# FI-pi_Milanpreet_Singh.net
KiCad netlist of a schematic drawn in EAGLE
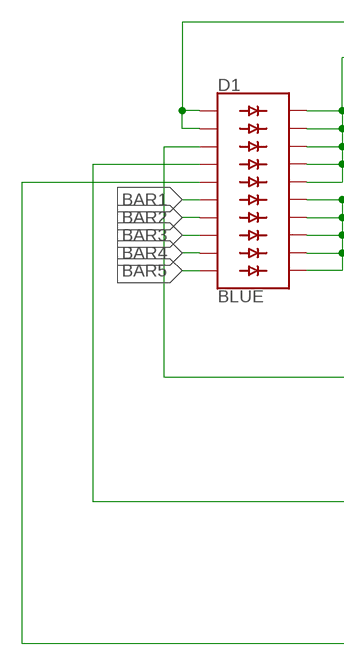
[diagram p0: schematic, sheet 1, part 1 of 2]
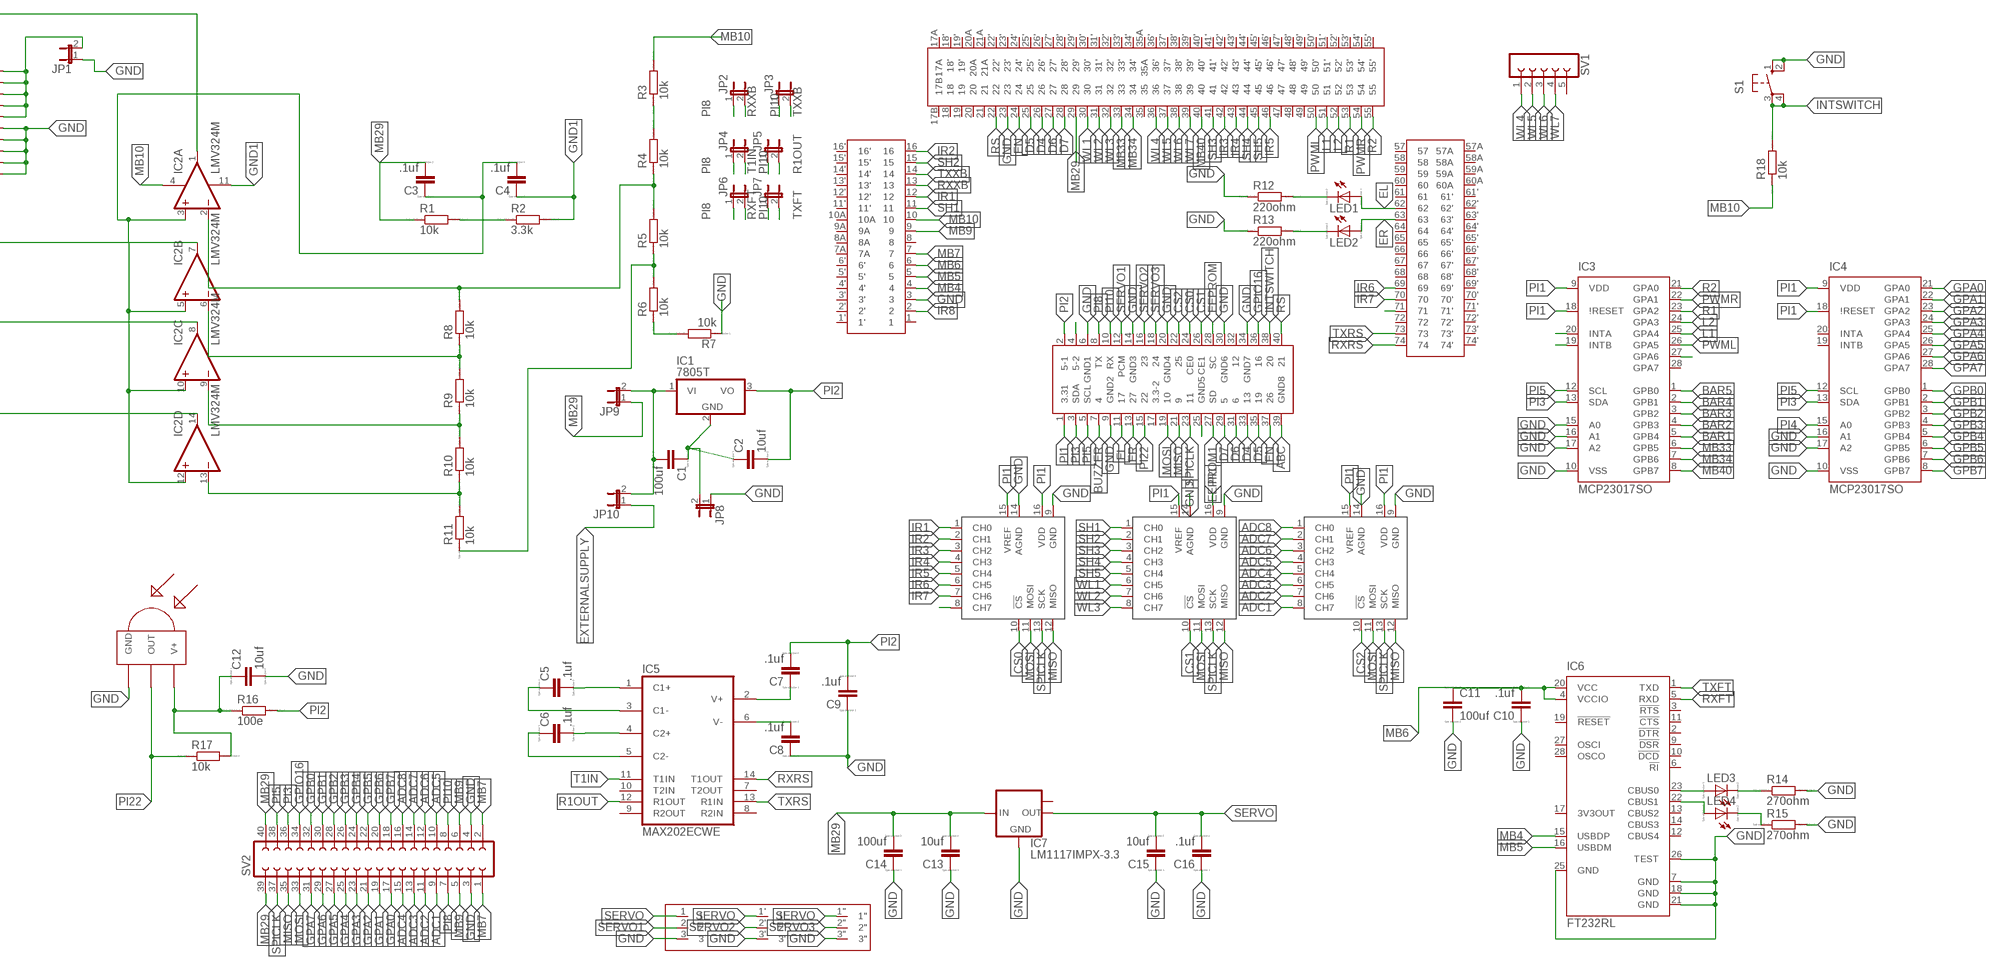
[diagram p1: schematic, sheet 1, part 2 of 2]

(export (version "E")
  (design (tool "Eeschema 10.0.6"))
  (components
    (comp (ref "C1")
      (value "100uf")
      (footprint "eagle-import:C1206")
      (libsource (lib "eagle-import") (part "CC1206"))
    )
    (comp (ref "C2")
      (value "10uf")
      (footprint "eagle-import:C1206")
      (libsource (lib "eagle-import") (part "CC1206"))
    )
    (comp (ref "C3")
      (value ".1uf")
      (footprint "eagle-import:C1206")
      (libsource (lib "eagle-import") (part "CC1206"))
    )
    (comp (ref "C4")
      (value ".1uf")
      (footprint "eagle-import:C1206")
      (libsource (lib "eagle-import") (part "CC1206"))
    )
    (comp (ref "C5")
      (value ".1uf")
      (footprint "eagle-import:C1206")
      (libsource (lib "eagle-import") (part "CC1206"))
    )
    (comp (ref "C6")
      (value ".1uf")
      (footprint "eagle-import:C1206")
      (libsource (lib "eagle-import") (part "CC1206"))
    )
    (comp (ref "C7")
      (value ".1uf")
      (footprint "eagle-import:C1206")
      (libsource (lib "eagle-import") (part "CC1206"))
    )
    (comp (ref "C8")
      (value ".1uf")
      (footprint "eagle-import:C1206")
      (libsource (lib "eagle-import") (part "CC1206"))
    )
    (comp (ref "C9")
      (value ".1uf")
      (footprint "eagle-import:C1206")
      (libsource (lib "eagle-import") (part "CC1206"))
    )
    (comp (ref "C10")
      (value ".1uf")
      (footprint "eagle-import:C1206")
      (libsource (lib "eagle-import") (part "CC1206"))
    )
    (comp (ref "C11")
      (value "100uf")
      (footprint "eagle-import:C1206")
      (libsource (lib "eagle-import") (part "CC1206"))
    )
    (comp (ref "C12")
      (value "10uf")
      (footprint "eagle-import:C1206")
      (libsource (lib "eagle-import") (part "CC1206"))
    )
    (comp (ref "C13")
      (value "10uf")
      (footprint "eagle-import:C1206")
      (libsource (lib "eagle-import") (part "CC1206"))
    )
    (comp (ref "C14")
      (value "100uf")
      (footprint "eagle-import:C1206")
      (libsource (lib "eagle-import") (part "CC1206"))
    )
    (comp (ref "C15")
      (value "10uf")
      (footprint "eagle-import:C1206")
      (libsource (lib "eagle-import") (part "CC1206"))
    )
    (comp (ref "C16")
      (value ".1uf")
      (footprint "eagle-import:C1206")
      (libsource (lib "eagle-import") (part "CC1206"))
    )
    (comp (ref "D1")
      (value "BLUE")
      (footprint "eagle-import:LED_BARGRAPH_10")
      (libsource (lib "eagle-import") (part "LED_BARGRAPH_10BLUE"))
    )
    (comp (ref "IC1")
      (value "7805T")
      (footprint "eagle-import:TO220H")
      (libsource (lib "eagle-import") (part "78T05"))
    )
    (comp (ref "IC2")
      (value "LMV324M")
      (footprint "eagle-import:SO14")
      (libsource (lib "eagle-import") (part "LMV324?M"))
    )
    (comp (ref "IC3")
      (value "MCP23017SO")
      (footprint "eagle-import:SO28W")
      (libsource (lib "eagle-import") (part "MCP23017SO"))
    )
    (comp (ref "IC4")
      (value "MCP23017SO")
      (footprint "eagle-import:SO28W")
      (libsource (lib "eagle-import") (part "MCP23017SO"))
    )
    (comp (ref "IC5")
      (value "MAX202ECWE")
      (footprint "eagle-import:SO16L")
      (fields (field (name "MPN") "MAX202ECWE+T"))
      (libsource (lib "eagle-import") (part "MAX202ECWE"))
    )
    (comp (ref "IC6")
      (value "FT232RL")
      (footprint "eagle-import:SSOP28")
      (libsource (lib "eagle-import") (part "FT232RL"))
    )
    (comp (ref "IC7")
      (value "LM1117IMPX-3.3")
      (footprint "eagle-import:SOT223")
      (libsource (lib "eagle-import") (part "LM1117IMPX-3.3"))
    )
    (comp (ref "JP1")
      (value "JP1E")
      (footprint "eagle-import:JP1")
      (libsource (lib "eagle-import") (part "JP1E"))
    )
    (comp (ref "JP2")
      (value "JP1E")
      (footprint "eagle-import:JP1")
      (libsource (lib "eagle-import") (part "JP1E"))
    )
    (comp (ref "JP3")
      (value "JP1E")
      (footprint "eagle-import:JP1")
      (libsource (lib "eagle-import") (part "JP1E"))
    )
    (comp (ref "JP4")
      (value "JP1E")
      (footprint "eagle-import:JP1")
      (libsource (lib "eagle-import") (part "JP1E"))
    )
    (comp (ref "JP5")
      (value "JP1E")
      (footprint "eagle-import:JP1")
      (libsource (lib "eagle-import") (part "JP1E"))
    )
    (comp (ref "JP6")
      (value "JP1E")
      (footprint "eagle-import:JP1")
      (libsource (lib "eagle-import") (part "JP1E"))
    )
    (comp (ref "JP7")
      (value "JP1E")
      (footprint "eagle-import:JP1")
      (libsource (lib "eagle-import") (part "JP1E"))
    )
    (comp (ref "JP8")
      (value "JP1E")
      (footprint "eagle-import:JP1")
      (libsource (lib "eagle-import") (part "JP1E"))
    )
    (comp (ref "JP9")
      (value "JP1E")
      (footprint "eagle-import:JP1")
      (libsource (lib "eagle-import") (part "JP1E"))
    )
    (comp (ref "JP10")
      (value "JP1E")
      (footprint "eagle-import:JP1")
      (libsource (lib "eagle-import") (part "JP1E"))
    )
    (comp (ref "LED1")
      (value "LED_E")
      (footprint "eagle-import:LED_1206")
      (libsource (lib "eagle-import") (part "LED_E"))
    )
    (comp (ref "LED2")
      (value "LED_E")
      (footprint "eagle-import:LED_1206")
      (libsource (lib "eagle-import") (part "LED_E"))
    )
    (comp (ref "LED3")
      (value "LED_E")
      (footprint "eagle-import:LED_1206")
      (libsource (lib "eagle-import") (part "LED_E"))
    )
    (comp (ref "LED4")
      (value "LED_E")
      (footprint "eagle-import:LED_1206")
      (libsource (lib "eagle-import") (part "LED_E"))
    )
    (comp (ref "R1")
      (value "10k")
      (footprint "eagle-import:R1206")
      (libsource (lib "eagle-import") (part "RR1206"))
    )
    (comp (ref "R2")
      (value "3.3k")
      (footprint "eagle-import:R1206")
      (libsource (lib "eagle-import") (part "RR1206"))
    )
    (comp (ref "R3")
      (value "10k")
      (footprint "eagle-import:R1206")
      (libsource (lib "eagle-import") (part "RR1206"))
    )
    (comp (ref "R4")
      (value "10k")
      (footprint "eagle-import:R1206")
      (libsource (lib "eagle-import") (part "RR1206"))
    )
    (comp (ref "R5")
      (value "10k")
      (footprint "eagle-import:R1206")
      (libsource (lib "eagle-import") (part "RR1206"))
    )
    (comp (ref "R6")
      (value "10k")
      (footprint "eagle-import:R1206")
      (libsource (lib "eagle-import") (part "RR1206"))
    )
    (comp (ref "R7")
      (value "10k")
      (footprint "eagle-import:R1206")
      (libsource (lib "eagle-import") (part "RR1206"))
    )
    (comp (ref "R8")
      (value "10k")
      (footprint "eagle-import:R1206")
      (libsource (lib "eagle-import") (part "RR1206"))
    )
    (comp (ref "R9")
      (value "10k")
      (footprint "eagle-import:R1206")
      (libsource (lib "eagle-import") (part "RR1206"))
    )
    (comp (ref "R10")
      (value "10k")
      (footprint "eagle-import:R1206")
      (libsource (lib "eagle-import") (part "RR1206"))
    )
    (comp (ref "R11")
      (value "10k")
      (footprint "eagle-import:R1206")
      (libsource (lib "eagle-import") (part "RR1206"))
    )
    (comp (ref "R12")
      (value "220ohm")
      (footprint "eagle-import:R1206")
      (libsource (lib "eagle-import") (part "RR1206"))
    )
    (comp (ref "R13")
      (value "220ohm")
      (footprint "eagle-import:R1206")
      (libsource (lib "eagle-import") (part "RR1206"))
    )
    (comp (ref "R14")
      (value "270ohm")
      (footprint "eagle-import:R1206")
      (libsource (lib "eagle-import") (part "RR1206"))
    )
    (comp (ref "R15")
      (value "270ohm")
      (footprint "eagle-import:R1206")
      (libsource (lib "eagle-import") (part "RR1206"))
    )
    (comp (ref "R16")
      (value "100e")
      (footprint "eagle-import:R1206")
      (libsource (lib "eagle-import") (part "RR1206"))
    )
    (comp (ref "R17")
      (value "10k")
      (footprint "eagle-import:R1206")
      (libsource (lib "eagle-import") (part "RR1206"))
    )
    (comp (ref "R18")
      (value "10k")
      (footprint "eagle-import:R1206")
      (libsource (lib "eagle-import") (part "RR1206"))
    )
    (comp (ref "S1")
      (value "10-XX")
      (footprint "eagle-import:B3F-10XX")
      (fields (field (name "MPN") "B3F-1000"))
      (libsource (lib "eagle-import") (part "10-XX"))
    )
    (comp (ref "SV1")
      (value "FE05-1")
      (footprint "eagle-import:FE05-1")
      (libsource (lib "eagle-import") (part "FE05-1"))
    )
    (comp (ref "SV2")
      (value "FE20-2")
      (footprint "eagle-import:FE20-2")
      (libsource (lib "eagle-import") (part "FE20-2"))
    )
    (comp (ref "U$1")
      (value "DAUGHTERBOARDDAUGHTERBOARD")
      (footprint "eagle-import:DAUGHTERBOARD")
      (libsource (lib "eagle-import") (part "DAUGHTERBOARDDAUGHTERBOARD"))
    )
    (comp (ref "U$2")
      (value "MALE_HEADER")
      (footprint "eagle-import:MALE_HEADER_PACKAGE")
      (libsource (lib "eagle-import") (part "MALE_HEADER"))
    )
    (comp (ref "U$3")
      (value "MCP3008SL")
      (footprint "eagle-import:SO16")
      (libsource (lib "eagle-import") (part "MCP3008SL"))
    )
    (comp (ref "U$4")
      (value "MCP3008SL")
      (footprint "eagle-import:SO16")
      (libsource (lib "eagle-import") (part "MCP3008SL"))
    )
    (comp (ref "U$5")
      (value "MCP3008SL")
      (footprint "eagle-import:SO16")
      (libsource (lib "eagle-import") (part "MCP3008SL"))
    )
    (comp (ref "U$6")
      (value "TSOP1738")
      (footprint "eagle-import:TSOP17XX")
      (libsource (lib "eagle-import") (part "TSOP1738"))
    )
    (comp (ref "U$7")
      (value "SERVO")
      (footprint "eagle-import:SERVO")
      (libsource (lib "eagle-import") (part "SERVO"))
    )
  )
  (nets
    (net (code "1") (name "ABC") (class "Default")
      (node (ref "U$2") (pin "39") (pinfunction "GND8_39") (pintype "bidirectional"))
    )
    (net (code "2") (name "ADC1") (class "Default")
      (node (ref "SV2") (pin "9") (pinfunction "9_9") (pintype "passive"))
      (node (ref "U$5") (pin "8") (pinfunction "CH7_8") (pintype "input"))
    )
    (net (code "3") (name "ADC2") (class "Default")
      (node (ref "SV2") (pin "11") (pinfunction "11_11") (pintype "passive"))
      (node (ref "U$5") (pin "7") (pinfunction "CH6_7") (pintype "input"))
    )
    (net (code "4") (name "ADC3") (class "Default")
      (node (ref "SV2") (pin "13") (pinfunction "13_13") (pintype "passive"))
      (node (ref "U$5") (pin "6") (pinfunction "CH5_6") (pintype "input"))
    )
    (net (code "5") (name "ADC4") (class "Default")
      (node (ref "SV2") (pin "15") (pinfunction "15_15") (pintype "passive"))
      (node (ref "U$5") (pin "5") (pinfunction "CH4_5") (pintype "input"))
    )
    (net (code "6") (name "ADC5") (class "Default")
      (node (ref "SV2") (pin "10") (pinfunction "10_10") (pintype "passive"))
      (node (ref "U$5") (pin "4") (pinfunction "CH3_4") (pintype "input"))
    )
    (net (code "7") (name "ADC6") (class "Default")
      (node (ref "SV2") (pin "12") (pinfunction "12_12") (pintype "passive"))
      (node (ref "U$5") (pin "3") (pinfunction "CH2_3") (pintype "input"))
    )
    (net (code "8") (name "ADC7") (class "Default")
      (node (ref "SV2") (pin "14") (pinfunction "14_14") (pintype "passive"))
      (node (ref "U$5") (pin "2") (pinfunction "CH1_2") (pintype "input"))
    )
    (net (code "9") (name "ADC8") (class "Default")
      (node (ref "SV2") (pin "16") (pinfunction "16_16") (pintype "passive"))
      (node (ref "U$5") (pin "1") (pinfunction "CH0_1") (pintype "input"))
    )
    (net (code "10") (name "BAR1") (class "Default")
      (node (ref "D1") (pin "6") (pinfunction "A5_6") (pintype "passive"))
      (node (ref "IC3") (pin "5") (pinfunction "GPB4_5") (pintype "bidirectional"))
    )
    (net (code "11") (name "BAR2") (class "Default")
      (node (ref "D1") (pin "7") (pinfunction "A6_7") (pintype "passive"))
      (node (ref "IC3") (pin "4") (pinfunction "GPB3_4") (pintype "bidirectional"))
    )
    (net (code "12") (name "BAR3") (class "Default")
      (node (ref "D1") (pin "8") (pinfunction "A7_8") (pintype "passive"))
      (node (ref "IC3") (pin "3") (pinfunction "GPB2_3") (pintype "bidirectional"))
    )
    (net (code "13") (name "BAR4") (class "Default")
      (node (ref "D1") (pin "9") (pinfunction "A8_9") (pintype "passive"))
      (node (ref "IC3") (pin "2") (pinfunction "GPB1_2") (pintype "bidirectional"))
    )
    (net (code "14") (name "BAR5") (class "Default")
      (node (ref "D1") (pin "10") (pinfunction "A9_10") (pintype "passive"))
      (node (ref "IC3") (pin "1") (pinfunction "GPB0_1") (pintype "bidirectional"))
    )
    (net (code "15") (name "BUZZER") (class "Default")
      (node (ref "U$1") (pin "71") (pinfunction "71_71") (pintype "output"))
      (node (ref "U$2") (pin "7") (pinfunction "4_7") (pintype "bidirectional"))
    )
    (net (code "16") (name "CS0") (class "Default")
      (node (ref "U$2") (pin "24") (pinfunction "CE0_24") (pintype "bidirectional"))
      (node (ref "U$3") (pin "10") (pinfunction "~{CS}_10") (pintype "input"))
    )
    (net (code "17") (name "CS1") (class "Default")
      (node (ref "U$2") (pin "26") (pinfunction "CE1_26") (pintype "bidirectional"))
      (node (ref "U$4") (pin "10") (pinfunction "~{CS}_10") (pintype "input"))
    )
    (net (code "18") (name "CS2") (class "Default")
      (node (ref "U$2") (pin "22") (pinfunction "25_22") (pintype "bidirectional"))
      (node (ref "U$5") (pin "10") (pinfunction "~{CS}_10") (pintype "input"))
    )
    (net (code "19") (name "D4") (class "Default")
      (node (ref "U$1") (pin "26") (pinfunction "26_26") (pintype "output"))
      (node (ref "U$2") (pin "33") (pinfunction "13_33") (pintype "bidirectional"))
    )
    (net (code "20") (name "D5") (class "Default")
      (node (ref "U$1") (pin "25") (pinfunction "25_25") (pintype "output"))
      (node (ref "U$2") (pin "35") (pinfunction "19_35") (pintype "bidirectional"))
    )
    (net (code "21") (name "D6") (class "Default")
      (node (ref "U$1") (pin "27") (pinfunction "27_27") (pintype "output"))
      (node (ref "U$2") (pin "31") (pinfunction "6_31") (pintype "bidirectional"))
    )
    (net (code "22") (name "D7") (class "Default")
      (node (ref "U$1") (pin "28") (pinfunction "28_28") (pintype "output"))
      (node (ref "U$2") (pin "29") (pinfunction "5_29") (pintype "bidirectional"))
    )
    (net (code "23") (name "EEPROM") (class "Default")
      (node (ref "U$2") (pin "28") (pinfunction "SC_28") (pintype "bidirectional"))
    )
    (net (code "24") (name "EEPROM1") (class "Default")
      (node (ref "U$2") (pin "27") (pinfunction "SD_27") (pintype "bidirectional"))
    )
    (net (code "25") (name "EL") (class "Default")
      (node (ref "LED1") (pin "A") (pinfunction "A_A") (pintype "passive"))
      (node (ref "U$1") (pin "62") (pinfunction "62_62") (pintype "output"))
      (node (ref "U$2") (pin "11") (pinfunction "17_11") (pintype "bidirectional"))
    )
    (net (code "26") (name "EN") (class "Default")
      (node (ref "U$1") (pin "24") (pinfunction "24_24") (pintype "output"))
      (node (ref "U$2") (pin "37") (pinfunction "26_37") (pintype "bidirectional"))
    )
    (net (code "27") (name "ER") (class "Default")
      (node (ref "LED2") (pin "A") (pinfunction "A_A") (pintype "passive"))
      (node (ref "U$1") (pin "63") (pinfunction "63_63") (pintype "output"))
      (node (ref "U$2") (pin "13") (pinfunction "27_13") (pintype "bidirectional"))
    )
    (net (code "28") (name "EXTERNALSUPPLY") (class "Default")
      (node (ref "JP10") (pin "1") (pinfunction "1_1") (pintype "passive"))
    )
    (net (code "29") (name "GND") (class "Default")
      (node (ref "C10") (pin "1") (pinfunction "1_1") (pintype "passive"))
      (node (ref "C11") (pin "2") (pinfunction "2_2") (pintype "passive"))
      (node (ref "C12") (pin "2") (pinfunction "2_2") (pintype "passive"))
      (node (ref "C13") (pin "1") (pinfunction "1_1") (pintype "passive"))
      (node (ref "C14") (pin "1") (pinfunction "1_1") (pintype "passive"))
      (node (ref "C15") (pin "1") (pinfunction "1_1") (pintype "passive"))
      (node (ref "C16") (pin "1") (pinfunction "1_1") (pintype "passive"))
      (node (ref "C8") (pin "1") (pinfunction "1_1") (pintype "passive"))
      (node (ref "C9") (pin "1") (pinfunction "1_1") (pintype "passive"))
      (node (ref "D1") (pin "11") (pinfunction "C9_11") (pintype "passive"))
      (node (ref "D1") (pin "12") (pinfunction "C8_12") (pintype "passive"))
      (node (ref "D1") (pin "13") (pinfunction "C7_13") (pintype "passive"))
      (node (ref "D1") (pin "14") (pinfunction "C6_14") (pintype "passive"))
      (node (ref "D1") (pin "15") (pinfunction "C5_15") (pintype "passive"))
      (node (ref "IC3") (pin "10") (pinfunction "VSS_10") (pintype "power_in"))
      (node (ref "IC3") (pin "15") (pinfunction "A0_15") (pintype "input"))
      (node (ref "IC3") (pin "16") (pinfunction "A1_16") (pintype "input"))
      (node (ref "IC3") (pin "17") (pinfunction "A2_17") (pintype "input"))
      (node (ref "IC4") (pin "10") (pinfunction "VSS_10") (pintype "power_in"))
      (node (ref "IC4") (pin "16") (pinfunction "A1_16") (pintype "input"))
      (node (ref "IC4") (pin "17") (pinfunction "A2_17") (pintype "input"))
      (node (ref "IC6") (pin "18") (pinfunction "GND_18") (pintype "power_in"))
      (node (ref "IC6") (pin "21") (pinfunction "GND_21") (pintype "power_in"))
      (node (ref "IC6") (pin "25") (pinfunction "GND_25") (pintype "power_in"))
      (node (ref "IC6") (pin "26") (pinfunction "TEST_26") (pintype "input"))
      (node (ref "IC6") (pin "7") (pinfunction "GND_7") (pintype "power_in"))
      (node (ref "IC7") (pin "1") (pinfunction "GND_1") (pintype "input"))
      (node (ref "JP1") (pin "1") (pinfunction "1_1") (pintype "passive"))
      (node (ref "JP8") (pin "1") (pinfunction "1_1") (pintype "passive"))
      (node (ref "R12") (pin "1") (pinfunction "1_1") (pintype "passive"))
      (node (ref "R13") (pin "1") (pinfunction "1_1") (pintype "passive"))
      (node (ref "R14") (pin "2") (pinfunction "2_2") (pintype "passive"))
      (node (ref "R15") (pin "2") (pinfunction "2_2") (pintype "passive"))
      (node (ref "R7") (pin "1") (pinfunction "1_1") (pintype "passive"))
      (node (ref "S1") (pin "1") (pinfunction "S_1") (pintype "passive"))
      (node (ref "S1") (pin "2") (pinfunction "S1_2") (pintype "passive"))
      (node (ref "SV2") (pin "3") (pinfunction "3_3") (pintype "passive"))
      (node (ref "SV2") (pin "4") (pinfunction "4_4") (pintype "passive"))
      (node (ref "U$1") (pin "23") (pinfunction "23_23") (pintype "output"))
      (node (ref "U$1") (pin "3") (pinfunction "3_3") (pintype "output"))
      (node (ref "U$2") (pin "14") (pinfunction "GND3_14") (pintype "bidirectional"))
      (node (ref "U$2") (pin "20") (pinfunction "GND4_20") (pintype "bidirectional"))
      (node (ref "U$2") (pin "25") (pinfunction "GND5_25") (pintype "bidirectional"))
      (node (ref "U$2") (pin "30") (pinfunction "GND6_30") (pintype "bidirectional"))
      (node (ref "U$2") (pin "34") (pinfunction "GND7_34") (pintype "bidirectional"))
      (node (ref "U$2") (pin "6") (pinfunction "GND1_6") (pintype "bidirectional"))
      (node (ref "U$2") (pin "9") (pinfunction "GND2_9") (pintype "bidirectional"))
      (node (ref "U$3") (pin "14") (pinfunction "AGND_14") (pintype "power_in"))
      (node (ref "U$3") (pin "9") (pinfunction "GND_9") (pintype "power_in"))
      (node (ref "U$4") (pin "14") (pinfunction "AGND_14") (pintype "power_in"))
      (node (ref "U$4") (pin "9") (pinfunction "GND_9") (pintype "power_in"))
      (node (ref "U$5") (pin "14") (pinfunction "AGND_14") (pintype "power_in"))
      (node (ref "U$5") (pin "9") (pinfunction "GND_9") (pintype "power_in"))
      (node (ref "U$6") (pin "GND") (pinfunction "GND_GND") (pintype "bidirectional"))
      (node (ref "U$7") (pin "3") (pinfunction "3_3") (pintype "bidirectional"))
      (node (ref "U$7") (pin "3\"") (pinfunction "3\"_3\"") (pintype "bidirectional"))
      (node (ref "U$7") (pin "3'") (pinfunction "3'_3'") (pintype "bidirectional"))
    )
    (net (code "30") (name "GND1") (class "Default")
      (node (ref "C4") (pin "1") (pinfunction "1_1") (pintype "passive"))
      (node (ref "IC2") (pin "11") (pinfunction "V-_11") (pintype "power_in"))
      (node (ref "R2") (pin "2") (pinfunction "2_2") (pintype "passive"))
    )
    (net (code "31") (name "GPA0") (class "Default")
      (node (ref "IC4") (pin "21") (pinfunction "GPA0_21") (pintype "bidirectional"))
      (node (ref "SV2") (pin "17") (pinfunction "17_17") (pintype "passive"))
    )
    (net (code "32") (name "GPA1") (class "Default")
      (node (ref "IC4") (pin "22") (pinfunction "GPA1_22") (pintype "bidirectional"))
      (node (ref "SV2") (pin "19") (pinfunction "19_19") (pintype "passive"))
    )
    (net (code "33") (name "GPA2") (class "Default")
      (node (ref "IC4") (pin "23") (pinfunction "GPA2_23") (pintype "bidirectional"))
      (node (ref "SV2") (pin "21") (pinfunction "21_21") (pintype "passive"))
    )
    (net (code "34") (name "GPA3") (class "Default")
      (node (ref "IC4") (pin "24") (pinfunction "GPA3_24") (pintype "bidirectional"))
      (node (ref "SV2") (pin "23") (pinfunction "23_23") (pintype "passive"))
    )
    (net (code "35") (name "GPA4") (class "Default")
      (node (ref "IC4") (pin "25") (pinfunction "GPA4_25") (pintype "bidirectional"))
      (node (ref "SV2") (pin "25") (pinfunction "25_25") (pintype "passive"))
    )
    (net (code "36") (name "GPA5") (class "Default")
      (node (ref "IC4") (pin "26") (pinfunction "GPA5_26") (pintype "bidirectional"))
      (node (ref "SV2") (pin "27") (pinfunction "27_27") (pintype "passive"))
    )
    (net (code "37") (name "GPA6") (class "Default")
      (node (ref "IC4") (pin "27") (pinfunction "GPA6_27") (pintype "bidirectional"))
      (node (ref "SV2") (pin "29") (pinfunction "29_29") (pintype "passive"))
    )
    (net (code "38") (name "GPA7") (class "Default")
      (node (ref "IC4") (pin "28") (pinfunction "GPA7_28") (pintype "bidirectional"))
      (node (ref "SV2") (pin "31") (pinfunction "31_31") (pintype "passive"))
    )
    (net (code "39") (name "GPB0") (class "Default")
      (node (ref "IC4") (pin "1") (pinfunction "GPB0_1") (pintype "bidirectional"))
      (node (ref "SV2") (pin "32") (pinfunction "32_32") (pintype "passive"))
    )
    (net (code "40") (name "GPB1") (class "Default")
      (node (ref "IC4") (pin "2") (pinfunction "GPB1_2") (pintype "bidirectional"))
      (node (ref "SV2") (pin "30") (pinfunction "30_30") (pintype "passive"))
    )
    (net (code "41") (name "GPB2") (class "Default")
      (node (ref "IC4") (pin "3") (pinfunction "GPB2_3") (pintype "bidirectional"))
      (node (ref "SV2") (pin "28") (pinfunction "28_28") (pintype "passive"))
    )
    (net (code "42") (name "GPB3") (class "Default")
      (node (ref "IC4") (pin "4") (pinfunction "GPB3_4") (pintype "bidirectional"))
      (node (ref "SV2") (pin "26") (pinfunction "26_26") (pintype "passive"))
    )
    (net (code "43") (name "GPB4") (class "Default")
      (node (ref "IC4") (pin "5") (pinfunction "GPB4_5") (pintype "bidirectional"))
      (node (ref "SV2") (pin "24") (pinfunction "24_24") (pintype "passive"))
    )
    (net (code "44") (name "GPB5") (class "Default")
      (node (ref "IC4") (pin "6") (pinfunction "GPB5_6") (pintype "bidirectional"))
      (node (ref "SV2") (pin "22") (pinfunction "22_22") (pintype "passive"))
    )
    (net (code "45") (name "GPB6") (class "Default")
      (node (ref "IC4") (pin "7") (pinfunction "GPB6_7") (pintype "bidirectional"))
      (node (ref "SV2") (pin "20") (pinfunction "20_20") (pintype "passive"))
    )
    (net (code "46") (name "GPB7") (class "Default")
      (node (ref "IC4") (pin "8") (pinfunction "GPB7_8") (pintype "bidirectional"))
      (node (ref "SV2") (pin "18") (pinfunction "18_18") (pintype "passive"))
    )
    (net (code "47") (name "GPIO16") (class "Default")
      (node (ref "SV2") (pin "34") (pinfunction "34_34") (pintype "passive"))
      (node (ref "U$2") (pin "36") (pinfunction "16_36") (pintype "bidirectional"))
    )
    (net (code "48") (name "INTSWITCH") (class "Default")
      (node (ref "R18") (pin "2") (pinfunction "2_2") (pintype "passive"))
      (node (ref "S1") (pin "3") (pinfunction "P_3") (pintype "passive"))
      (node (ref "S1") (pin "4") (pinfunction "P1_4") (pintype "passive"))
      (node (ref "U$2") (pin "38") (pinfunction "20_38") (pintype "bidirectional"))
    )
    (net (code "49") (name "IR1") (class "Default")
      (node (ref "U$1") (pin "12") (pinfunction "12_12") (pintype "output"))
      (node (ref "U$3") (pin "1") (pinfunction "CH0_1") (pintype "input"))
    )
    (net (code "50") (name "IR2") (class "Default")
      (node (ref "U$1") (pin "16") (pinfunction "16_16") (pintype "output"))
      (node (ref "U$3") (pin "2") (pinfunction "CH1_2") (pintype "input"))
    )
    (net (code "51") (name "IR3") (class "Default")
      (node (ref "U$1") (pin "42") (pinfunction "42_42") (pintype "output"))
      (node (ref "U$3") (pin "3") (pinfunction "CH2_3") (pintype "input"))
    )
    (net (code "52") (name "IR4") (class "Default")
      (node (ref "U$1") (pin "43") (pinfunction "43_43") (pintype "output"))
      (node (ref "U$3") (pin "4") (pinfunction "CH3_4") (pintype "input"))
    )
    (net (code "53") (name "IR5") (class "Default")
      (node (ref "U$1") (pin "46") (pinfunction "46_46") (pintype "output"))
      (node (ref "U$3") (pin "5") (pinfunction "CH4_5") (pintype "input"))
    )
    (net (code "54") (name "IR6") (class "Default")
      (node (ref "U$1") (pin "69") (pinfunction "69_69") (pintype "output"))
      (node (ref "U$3") (pin "6") (pinfunction "CH5_6") (pintype "input"))
    )
    (net (code "55") (name "IR7") (class "Default")
      (node (ref "U$1") (pin "70") (pinfunction "70_70") (pintype "output"))
      (node (ref "U$3") (pin "7") (pinfunction "CH6_7") (pintype "input"))
    )
    (net (code "56") (name "IR8") (class "Default")
      (node (ref "U$1") (pin "2") (pinfunction "2_2") (pintype "output"))
      (node (ref "U$3") (pin "8") (pinfunction "CH7_8") (pintype "input"))
    )
    (net (code "57") (name "L1") (class "Default")
      (node (ref "IC3") (pin "25") (pinfunction "GPA4_25") (pintype "bidirectional"))
      (node (ref "U$1") (pin "51") (pinfunction "51_51") (pintype "output"))
    )
    (net (code "58") (name "L2") (class "Default")
      (node (ref "IC3") (pin "24") (pinfunction "GPA3_24") (pintype "bidirectional"))
      (node (ref "U$1") (pin "52") (pinfunction "52_52") (pintype "output"))
    )
    (net (code "59") (name "MB4") (class "Default")
      (node (ref "IC6") (pin "15") (pinfunction "USBDP_15") (pintype "bidirectional"))
      (node (ref "U$1") (pin "4") (pinfunction "4_4") (pintype "output"))
    )
    (net (code "60") (name "MB5") (class "Default")
      (node (ref "IC6") (pin "16") (pinfunction "USBDM_16") (pintype "bidirectional"))
      (node (ref "U$1") (pin "5") (pinfunction "5_5") (pintype "output"))
    )
    (net (code "61") (name "MB6") (class "Default")
      (node (ref "C10") (pin "2") (pinfunction "2_2") (pintype "passive"))
      (node (ref "C11") (pin "1") (pinfunction "1_1") (pintype "passive"))
      (node (ref "IC6") (pin "20") (pinfunction "VCC_20") (pintype "power_in"))
      (node (ref "IC6") (pin "4") (pinfunction "VCCIO_4") (pintype "power_in"))
      (node (ref "U$1") (pin "6") (pinfunction "6_6") (pintype "output"))
    )
    (net (code "62") (name "MB7") (class "Default")
      (node (ref "SV2") (pin "1") (pinfunction "1_1") (pintype "passive"))
      (node (ref "SV2") (pin "2") (pinfunction "2_2") (pintype "passive"))
      (node (ref "U$1") (pin "7") (pinfunction "7_7") (pintype "output"))
    )
    (net (code "63") (name "MB9") (class "Default")
      (node (ref "SV2") (pin "5") (pinfunction "5_5") (pintype "passive"))
      (node (ref "SV2") (pin "6") (pinfunction "6_6") (pintype "passive"))
      (node (ref "U$1") (pin "9") (pinfunction "9_9") (pintype "output"))
    )
    (net (code "64") (name "MB10") (class "Default")
      (node (ref "IC2") (pin "4") (pinfunction "V+_4") (pintype "power_in"))
      (node (ref "R18") (pin "1") (pinfunction "1_1") (pintype "passive"))
      (node (ref "R3") (pin "2") (pinfunction "2_2") (pintype "passive"))
      (node (ref "U$1") (pin "10") (pinfunction "10_10") (pintype "output"))
    )
    (net (code "65") (name "MB29") (class "Default")
      (node (ref "C1") (pin "2") (pinfunction "2_2") (pintype "passive"))
      (node (ref "C13") (pin "2") (pinfunction "2_2") (pintype "passive"))
      (node (ref "C14") (pin "2") (pinfunction "2_2") (pintype "passive"))
      (node (ref "C3") (pin "2") (pinfunction "2_2") (pintype "passive"))
      (node (ref "IC1") (pin "1") (pinfunction "VI_1") (pintype "input"))
      (node (ref "IC7") (pin "3") (pinfunction "IN_3") (pintype "input"))
      (node (ref "JP10") (pin "2") (pinfunction "2_2") (pintype "passive"))
      (node (ref "JP9") (pin "1") (pinfunction "1_1") (pintype "passive"))
      (node (ref "JP9") (pin "2") (pinfunction "2_2") (pintype "passive"))
      (node (ref "R1") (pin "1") (pinfunction "1_1") (pintype "passive"))
      (node (ref "SV2") (pin "39") (pinfunction "39_39") (pintype "passive"))
      (node (ref "SV2") (pin "40") (pinfunction "40_40") (pintype "passive"))
      (node (ref "U$1") (pin "29") (pinfunction "29_29") (pintype "output"))
    )
    (net (code "66") (name "MB33") (class "Default")
      (node (ref "IC3") (pin "6") (pinfunction "GPB5_6") (pintype "bidirectional"))
      (node (ref "U$1") (pin "33") (pinfunction "33_33") (pintype "output"))
    )
    (net (code "67") (name "MB34") (class "Default")
      (node (ref "IC3") (pin "7") (pinfunction "GPB6_7") (pintype "bidirectional"))
      (node (ref "U$1") (pin "34") (pinfunction "34_34") (pintype "output"))
    )
    (net (code "68") (name "MB40") (class "Default")
      (node (ref "IC3") (pin "8") (pinfunction "GPB7_8") (pintype "bidirectional"))
      (node (ref "U$1") (pin "40") (pinfunction "40_40") (pintype "output"))
    )
    (net (code "69") (name "MISO") (class "Default")
      (node (ref "SV2") (pin "35") (pinfunction "35_35") (pintype "passive"))
      (node (ref "U$2") (pin "21") (pinfunction "9_21") (pintype "bidirectional"))
      (node (ref "U$3") (pin "12") (pinfunction "MISO_12") (pintype "output"))
      (node (ref "U$4") (pin "12") (pinfunction "MISO_12") (pintype "output"))
      (node (ref "U$5") (pin "12") (pinfunction "MISO_12") (pintype "output"))
    )
    (net (code "70") (name "MOSI") (class "Default")
      (node (ref "SV2") (pin "33") (pinfunction "33_33") (pintype "passive"))
      (node (ref "U$2") (pin "19") (pinfunction "10_19") (pintype "bidirectional"))
      (node (ref "U$3") (pin "11") (pinfunction "MOSI_11") (pintype "input"))
      (node (ref "U$4") (pin "11") (pinfunction "MOSI_11") (pintype "input"))
      (node (ref "U$5") (pin "11") (pinfunction "MOSI_11") (pintype "input"))
    )
    (net (code "71") (name "Net-(C12-Pad1)") (class "Default")
      (node (ref "C12") (pin "1") (pinfunction "1_1") (pintype "passive"))
      (node (ref "R16") (pin "1") (pinfunction "1_1") (pintype "passive"))
      (node (ref "R17") (pin "2") (pinfunction "2_2") (pintype "passive"))
      (node (ref "U$6") (pin "V+") (pinfunction "V+_V+") (pintype "bidirectional"))
    )
    (net (code "72") (name "Net-(D1-A)") (class "Default")
      (node (ref "D1") (pin "1") (pinfunction "A_1") (pintype "passive"))
      (node (ref "D1") (pin "2") (pinfunction "A1_2") (pintype "passive"))
      (node (ref "IC2") (pin "1") (pinfunction "OUT_1") (pintype "output"))
    )
    (net (code "73") (name "Net-(D1-A2)") (class "Default")
      (node (ref "D1") (pin "3") (pinfunction "A2_3") (pintype "passive"))
      (node (ref "IC2") (pin "7") (pinfunction "OUT_7") (pintype "output"))
    )
    (net (code "74") (name "Net-(D1-A3)") (class "Default")
      (node (ref "D1") (pin "4") (pinfunction "A3_4") (pintype "passive"))
      (node (ref "IC2") (pin "8") (pinfunction "OUT_8") (pintype "output"))
    )
    (net (code "75") (name "Net-(D1-A4)") (class "Default")
      (node (ref "D1") (pin "5") (pinfunction "A4_5") (pintype "passive"))
      (node (ref "IC2") (pin "14") (pinfunction "OUT_14") (pintype "output"))
    )
    (net (code "76") (name "Net-(D1-C)") (class "Default")
      (node (ref "D1") (pin "16") (pinfunction "C4_16") (pintype "passive"))
      (node (ref "D1") (pin "17") (pinfunction "C3_17") (pintype "passive"))
      (node (ref "D1") (pin "18") (pinfunction "C2_18") (pintype "passive"))
      (node (ref "D1") (pin "19") (pinfunction "C1_19") (pintype "passive"))
      (node (ref "D1") (pin "20") (pinfunction "C_20") (pintype "passive"))
      (node (ref "JP1") (pin "2") (pinfunction "2_2") (pintype "passive"))
    )
    (net (code "77") (name "Net-(IC1-GND)") (class "Default")
      (node (ref "C1") (pin "1") (pinfunction "1_1") (pintype "passive"))
      (node (ref "C2") (pin "1") (pinfunction "1_1") (pintype "passive"))
      (node (ref "IC1") (pin "2") (pinfunction "GND_2") (pintype "passive"))
      (node (ref "JP8") (pin "2") (pinfunction "2_2") (pintype "passive"))
    )
    (net (code "78") (name "Net-(IC2A-+IN)") (class "Default")
      (node (ref "C3") (pin "1") (pinfunction "1_1") (pintype "passive"))
      (node (ref "C4") (pin "2") (pinfunction "2_2") (pintype "passive"))
      (node (ref "IC2") (pin "10") (pinfunction "+IN_10") (pintype "input"))
      (node (ref "IC2") (pin "12") (pinfunction "+IN_12") (pintype "input"))
      (node (ref "IC2") (pin "3") (pinfunction "+IN_3") (pintype "input"))
      (node (ref "IC2") (pin "5") (pinfunction "+IN_5") (pintype "input"))
      (node (ref "R1") (pin "2") (pinfunction "2_2") (pintype "passive"))
      (node (ref "R2") (pin "1") (pinfunction "1_1") (pintype "passive"))
    )
    (net (code "79") (name "Net-(IC2A--IN)") (class "Default")
      (node (ref "IC2") (pin "2") (pinfunction "-IN_2") (pintype "input"))
      (node (ref "R4") (pin "1") (pinfunction "1_1") (pintype "passive"))
      (node (ref "R5") (pin "2") (pinfunction "2_2") (pintype "passive"))
      (node (ref "R8") (pin "2") (pinfunction "2_2") (pintype "passive"))
    )
    (net (code "80") (name "Net-(IC2B--IN)") (class "Default")
      (node (ref "IC2") (pin "6") (pinfunction "-IN_6") (pintype "input"))
      (node (ref "R8") (pin "1") (pinfunction "1_1") (pintype "passive"))
      (node (ref "R9") (pin "2") (pinfunction "2_2") (pintype "passive"))
    )
    (net (code "81") (name "Net-(IC2C--IN)") (class "Default")
      (node (ref "IC2") (pin "9") (pinfunction "-IN_9") (pintype "input"))
      (node (ref "R10") (pin "2") (pinfunction "2_2") (pintype "passive"))
      (node (ref "R9") (pin "1") (pinfunction "1_1") (pintype "passive"))
    )
    (net (code "82") (name "Net-(IC2D--IN)") (class "Default")
      (node (ref "IC2") (pin "13") (pinfunction "-IN_13") (pintype "input"))
      (node (ref "R10") (pin "1") (pinfunction "1_1") (pintype "passive"))
      (node (ref "R11") (pin "2") (pinfunction "2_2") (pintype "passive"))
    )
    (net (code "83") (name "Net-(IC5A-C1+)") (class "Default")
      (node (ref "C5") (pin "2") (pinfunction "2_2") (pintype "passive"))
      (node (ref "IC5") (pin "1") (pinfunction "C1+_1") (pintype "bidirectional"))
    )
    (net (code "84") (name "Net-(IC5A-C1-)") (class "Default")
      (node (ref "C5") (pin "1") (pinfunction "1_1") (pintype "passive"))
      (node (ref "IC5") (pin "3") (pinfunction "C1-_3") (pintype "bidirectional"))
    )
    (net (code "85") (name "Net-(IC5A-C2+)") (class "Default")
      (node (ref "C6") (pin "2") (pinfunction "2_2") (pintype "passive"))
      (node (ref "IC5") (pin "4") (pinfunction "C2+_4") (pintype "bidirectional"))
    )
    (net (code "86") (name "Net-(IC5A-C2-)") (class "Default")
      (node (ref "C6") (pin "1") (pinfunction "1_1") (pintype "passive"))
      (node (ref "IC5") (pin "5") (pinfunction "C2-_5") (pintype "bidirectional"))
    )
    (net (code "87") (name "Net-(IC5A-V+)") (class "Default")
      (node (ref "C7") (pin "1") (pinfunction "1_1") (pintype "passive"))
      (node (ref "IC5") (pin "2") (pinfunction "V+_2") (pintype "bidirectional"))
    )
    (net (code "88") (name "Net-(IC5A-V-)") (class "Default")
      (node (ref "C8") (pin "2") (pinfunction "2_2") (pintype "passive"))
      (node (ref "IC5") (pin "6") (pinfunction "V-_6") (pintype "bidirectional"))
    )
    (net (code "89") (name "Net-(IC6-CBUS0)") (class "Default")
      (node (ref "IC6") (pin "23") (pinfunction "CBUS0_23") (pintype "bidirectional"))
      (node (ref "LED3") (pin "A") (pinfunction "A_A") (pintype "passive"))
    )
    (net (code "90") (name "Net-(IC6-CBUS1)") (class "Default")
      (node (ref "IC6") (pin "22") (pinfunction "CBUS1_22") (pintype "bidirectional"))
      (node (ref "LED4") (pin "A") (pinfunction "A_A") (pintype "passive"))
    )
    (net (code "91") (name "Net-(LED1-PadC)") (class "Default")
      (node (ref "LED1") (pin "C") (pinfunction "C_C") (pintype "passive"))
      (node (ref "R12") (pin "2") (pinfunction "2_2") (pintype "passive"))
    )
    (net (code "92") (name "Net-(LED2-PadC)") (class "Default")
      (node (ref "LED2") (pin "C") (pinfunction "C_C") (pintype "passive"))
      (node (ref "R13") (pin "2") (pinfunction "2_2") (pintype "passive"))
    )
    (net (code "93") (name "Net-(LED3-PadC)") (class "Default")
      (node (ref "LED3") (pin "C") (pinfunction "C_C") (pintype "passive"))
      (node (ref "R14") (pin "1") (pinfunction "1_1") (pintype "passive"))
    )
    (net (code "94") (name "Net-(LED4-PadC)") (class "Default")
      (node (ref "LED4") (pin "C") (pinfunction "C_C") (pintype "passive"))
      (node (ref "R15") (pin "1") (pinfunction "1_1") (pintype "passive"))
    )
    (net (code "95") (name "Net-(R3-Pad1)") (class "Default")
      (node (ref "R3") (pin "1") (pinfunction "1_1") (pintype "passive"))
      (node (ref "R4") (pin "2") (pinfunction "2_2") (pintype "passive"))
    )
    (net (code "96") (name "Net-(R6-Pad1)") (class "Default")
      (node (ref "R6") (pin "1") (pinfunction "1_1") (pintype "passive"))
      (node (ref "R7") (pin "2") (pinfunction "2_2") (pintype "passive"))
    )
    (net (code "97") (name "Net-(R11-Pad1)") (class "Default")
      (node (ref "R11") (pin "1") (pinfunction "1_1") (pintype "passive"))
      (node (ref "R5") (pin "1") (pinfunction "1_1") (pintype "passive"))
      (node (ref "R6") (pin "2") (pinfunction "2_2") (pintype "passive"))
    )
    (net (code "98") (name "PI1") (class "Default")
      (node (ref "IC3") (pin "18") (pinfunction "\\~{RESET}_18") (pintype "input"))
      (node (ref "IC3") (pin "9") (pinfunction "VDD_9") (pintype "power_in"))
      (node (ref "IC4") (pin "18") (pinfunction "\\~{RESET}_18") (pintype "input"))
      (node (ref "IC4") (pin "9") (pinfunction "VDD_9") (pintype "power_in"))
      (node (ref "U$2") (pin "1") (pinfunction "3.31_1") (pintype "bidirectional"))
      (node (ref "U$3") (pin "15") (pinfunction "VREF_15") (pintype "power_in"))
      (node (ref "U$3") (pin "16") (pinfunction "VDD_16") (pintype "power_in"))
      (node (ref "U$4") (pin "15") (pinfunction "VREF_15") (pintype "power_in"))
      (node (ref "U$4") (pin "16") (pinfunction "VDD_16") (pintype "power_in"))
      (node (ref "U$5") (pin "15") (pinfunction "VREF_15") (pintype "power_in"))
      (node (ref "U$5") (pin "16") (pinfunction "VDD_16") (pintype "power_in"))
    )
    (net (code "99") (name "PI2") (class "Default")
      (node (ref "C2") (pin "2") (pinfunction "2_2") (pintype "passive"))
      (node (ref "C7") (pin "2") (pinfunction "2_2") (pintype "passive"))
      (node (ref "C9") (pin "2") (pinfunction "2_2") (pintype "passive"))
      (node (ref "IC1") (pin "3") (pinfunction "VO_3") (pintype "passive"))
      (node (ref "R16") (pin "2") (pinfunction "2_2") (pintype "passive"))
      (node (ref "U$2") (pin "2") (pinfunction "5-1_2") (pintype "bidirectional"))
    )
    (net (code "100") (name "PI3") (class "Default")
      (node (ref "IC3") (pin "13") (pinfunction "SDA_13") (pintype "bidirectional"))
      (node (ref "IC4") (pin "13") (pinfunction "SDA_13") (pintype "bidirectional"))
      (node (ref "SV2") (pin "36") (pinfunction "36_36") (pintype "passive"))
      (node (ref "U$2") (pin "3") (pinfunction "SDA_3") (pintype "bidirectional"))
    )
    (net (code "101") (name "PI4") (class "Default")
      (node (ref "IC4") (pin "15") (pinfunction "A0_15") (pintype "input"))
      (node (ref "U$2") (pin "4") (pinfunction "5-2_4") (pintype "bidirectional"))
    )
    (net (code "102") (name "PI5") (class "Default")
      (node (ref "IC3") (pin "12") (pinfunction "SCL_12") (pintype "input"))
      (node (ref "IC4") (pin "12") (pinfunction "SCL_12") (pintype "input"))
      (node (ref "SV2") (pin "38") (pinfunction "38_38") (pintype "passive"))
      (node (ref "U$2") (pin "5") (pinfunction "SCL_5") (pintype "bidirectional"))
    )
    (net (code "103") (name "PI8") (class "Default")
      (node (ref "JP2") (pin "1") (pinfunction "1_1") (pintype "passive"))
      (node (ref "JP4") (pin "1") (pinfunction "1_1") (pintype "passive"))
      (node (ref "JP6") (pin "1") (pinfunction "1_1") (pintype "passive"))
      (node (ref "SV2") (pin "7") (pinfunction "7_7") (pintype "passive"))
      (node (ref "U$2") (pin "8") (pinfunction "TX_8") (pintype "bidirectional"))
    )
    (net (code "104") (name "PI10") (class "Default")
      (node (ref "JP3") (pin "1") (pinfunction "1_1") (pintype "passive"))
      (node (ref "JP5") (pin "1") (pinfunction "1_1") (pintype "passive"))
      (node (ref "JP7") (pin "1") (pinfunction "1_1") (pintype "passive"))
      (node (ref "SV2") (pin "8") (pinfunction "8_8") (pintype "passive"))
      (node (ref "U$2") (pin "10") (pinfunction "RX_10") (pintype "bidirectional"))
    )
    (net (code "105") (name "PI22") (class "Default")
      (node (ref "R17") (pin "1") (pinfunction "1_1") (pintype "passive"))
      (node (ref "U$2") (pin "15") (pinfunction "22_15") (pintype "bidirectional"))
      (node (ref "U$6") (pin "OUT") (pinfunction "OUT_OUT") (pintype "bidirectional"))
    )
    (net (code "106") (name "PWML") (class "Default")
      (node (ref "IC3") (pin "26") (pinfunction "GPA5_26") (pintype "bidirectional"))
      (node (ref "U$1") (pin "50") (pinfunction "50_50") (pintype "output"))
    )
    (net (code "107") (name "PWMR") (class "Default")
      (node (ref "IC3") (pin "22") (pinfunction "GPA1_22") (pintype "bidirectional"))
      (node (ref "U$1") (pin "54") (pinfunction "54_54") (pintype "output"))
    )
    (net (code "108") (name "R1") (class "Default")
      (node (ref "IC3") (pin "23") (pinfunction "GPA2_23") (pintype "bidirectional"))
      (node (ref "U$1") (pin "53") (pinfunction "53_53") (pintype "output"))
    )
    (net (code "109") (name "R1OUT") (class "Default")
      (node (ref "IC5") (pin "12") (pinfunction "R1OUT_12") (pintype "output"))
      (node (ref "JP5") (pin "2") (pinfunction "2_2") (pintype "passive"))
    )
    (net (code "110") (name "R2") (class "Default")
      (node (ref "IC3") (pin "21") (pinfunction "GPA0_21") (pintype "bidirectional"))
      (node (ref "U$1") (pin "55") (pinfunction "55_55") (pintype "output"))
    )
    (net (code "111") (name "RS") (class "Default")
      (node (ref "U$1") (pin "22") (pinfunction "22_22") (pintype "output"))
      (node (ref "U$2") (pin "40") (pinfunction "21_40") (pintype "bidirectional"))
    )
    (net (code "112") (name "RXFT") (class "Default")
      (node (ref "IC6") (pin "5") (pinfunction "RXD_5") (pintype "input"))
      (node (ref "JP6") (pin "2") (pinfunction "2_2") (pintype "passive"))
    )
    (net (code "113") (name "RXRS") (class "Default")
      (node (ref "IC5") (pin "14") (pinfunction "T1OUT_14") (pintype "output"))
      (node (ref "U$1") (pin "74") (pinfunction "74_74") (pintype "output"))
    )
    (net (code "114") (name "RXXB") (class "Default")
      (node (ref "JP2") (pin "2") (pinfunction "2_2") (pintype "passive"))
      (node (ref "U$1") (pin "13") (pinfunction "13_13") (pintype "output"))
    )
    (net (code "115") (name "SERVO") (class "Default")
      (node (ref "C15") (pin "2") (pinfunction "2_2") (pintype "passive"))
      (node (ref "C16") (pin "2") (pinfunction "2_2") (pintype "passive"))
      (node (ref "IC7") (pin "2") (pinfunction "OUT_2") (pintype "passive"))
      (node (ref "U$7") (pin "1") (pinfunction "1_1") (pintype "bidirectional"))
      (node (ref "U$7") (pin "1\"") (pinfunction "1\"_1\"") (pintype "bidirectional"))
      (node (ref "U$7") (pin "1'") (pinfunction "1'_1'") (pintype "bidirectional"))
    )
    (net (code "116") (name "SERVO1") (class "Default")
      (node (ref "U$2") (pin "12") (pinfunction "PCM_12") (pintype "bidirectional"))
      (node (ref "U$7") (pin "2") (pinfunction "2_2") (pintype "bidirectional"))
    )
    (net (code "117") (name "SERVO2") (class "Default")
      (node (ref "U$2") (pin "16") (pinfunction "23_16") (pintype "bidirectional"))
      (node (ref "U$7") (pin "2'") (pinfunction "2'_2'") (pintype "bidirectional"))
    )
    (net (code "118") (name "SERVO3") (class "Default")
      (node (ref "U$2") (pin "18") (pinfunction "24_18") (pintype "bidirectional"))
      (node (ref "U$7") (pin "2\"") (pinfunction "2\"_2\"") (pintype "bidirectional"))
    )
    (net (code "119") (name "SH1") (class "Default")
      (node (ref "U$1") (pin "11") (pinfunction "11_11") (pintype "output"))
      (node (ref "U$4") (pin "1") (pinfunction "CH0_1") (pintype "input"))
    )
    (net (code "120") (name "SH2") (class "Default")
      (node (ref "U$1") (pin "15") (pinfunction "15_15") (pintype "output"))
      (node (ref "U$4") (pin "2") (pinfunction "CH1_2") (pintype "input"))
    )
    (net (code "121") (name "SH3") (class "Default")
      (node (ref "U$1") (pin "41") (pinfunction "41_41") (pintype "output"))
      (node (ref "U$4") (pin "3") (pinfunction "CH2_3") (pintype "input"))
    )
    (net (code "122") (name "SH4") (class "Default")
      (node (ref "U$1") (pin "44") (pinfunction "44_44") (pintype "output"))
      (node (ref "U$4") (pin "4") (pinfunction "CH3_4") (pintype "input"))
    )
    (net (code "123") (name "SH5") (class "Default")
      (node (ref "U$1") (pin "45") (pinfunction "45_45") (pintype "output"))
      (node (ref "U$4") (pin "5") (pinfunction "CH4_5") (pintype "input"))
    )
    (net (code "124") (name "SPICLK") (class "Default")
      (node (ref "SV2") (pin "37") (pinfunction "37_37") (pintype "passive"))
      (node (ref "U$2") (pin "23") (pinfunction "11_23") (pintype "bidirectional"))
      (node (ref "U$3") (pin "13") (pinfunction "SCK_13") (pintype "input"))
      (node (ref "U$4") (pin "13") (pinfunction "SCK_13") (pintype "input"))
      (node (ref "U$5") (pin "13") (pinfunction "SCK_13") (pintype "input"))
    )
    (net (code "125") (name "T1IN") (class "Default")
      (node (ref "IC5") (pin "11") (pinfunction "T1IN_11") (pintype "input"))
      (node (ref "JP4") (pin "2") (pinfunction "2_2") (pintype "passive"))
    )
    (net (code "126") (name "TXFT") (class "Default")
      (node (ref "IC6") (pin "1") (pinfunction "TXD_1") (pintype "output"))
      (node (ref "JP7") (pin "2") (pinfunction "2_2") (pintype "passive"))
    )
    (net (code "127") (name "TXRS") (class "Default")
      (node (ref "IC5") (pin "13") (pinfunction "R1IN_13") (pintype "input"))
      (node (ref "U$1") (pin "73") (pinfunction "73_73") (pintype "output"))
    )
    (net (code "128") (name "TXXB") (class "Default")
      (node (ref "JP3") (pin "2") (pinfunction "2_2") (pintype "passive"))
      (node (ref "U$1") (pin "14") (pinfunction "14_14") (pintype "output"))
    )
    (net (code "129") (name "WL1") (class "Default")
      (node (ref "U$1") (pin "30") (pinfunction "30_30") (pintype "output"))
      (node (ref "U$4") (pin "6") (pinfunction "CH5_6") (pintype "input"))
    )
    (net (code "130") (name "WL2") (class "Default")
      (node (ref "U$1") (pin "31") (pinfunction "31_31") (pintype "output"))
      (node (ref "U$4") (pin "7") (pinfunction "CH6_7") (pintype "input"))
    )
    (net (code "131") (name "WL3") (class "Default")
      (node (ref "U$1") (pin "32") (pinfunction "32_32") (pintype "output"))
      (node (ref "U$4") (pin "8") (pinfunction "CH7_8") (pintype "input"))
    )
    (net (code "132") (name "WL4") (class "Default")
      (node (ref "SV1") (pin "1") (pinfunction "1_1") (pintype "passive"))
      (node (ref "U$1") (pin "36") (pinfunction "36_36") (pintype "output"))
    )
    (net (code "133") (name "WL5") (class "Default")
      (node (ref "SV1") (pin "2") (pinfunction "2_2") (pintype "passive"))
      (node (ref "U$1") (pin "37") (pinfunction "37_37") (pintype "output"))
    )
    (net (code "134") (name "WL6") (class "Default")
      (node (ref "SV1") (pin "3") (pinfunction "3_3") (pintype "passive"))
      (node (ref "U$1") (pin "38") (pinfunction "38_38") (pintype "output"))
    )
    (net (code "135") (name "WL7") (class "Default")
      (node (ref "SV1") (pin "4") (pinfunction "4_4") (pintype "passive"))
      (node (ref "U$1") (pin "39") (pinfunction "39_39") (pintype "output"))
    )
    (net (code "136") (name "unconnected-(IC3-GPA6-Pad27)") (class "Default")
      (node (ref "IC3") (pin "27") (pinfunction "GPA6_27") (pintype "bidirectional"))
    )
    (net (code "137") (name "unconnected-(IC3-GPA7-Pad28)") (class "Default")
      (node (ref "IC3") (pin "28") (pinfunction "GPA7_28") (pintype "bidirectional"))
    )
    (net (code "138") (name "unconnected-(IC3-INTA-Pad20)") (class "Default")
      (node (ref "IC3") (pin "20") (pinfunction "INTA_20") (pintype "output"))
    )
    (net (code "139") (name "unconnected-(IC3-INTB-Pad19)") (class "Default")
      (node (ref "IC3") (pin "19") (pinfunction "INTB_19") (pintype "output"))
    )
    (net (code "140") (name "unconnected-(IC4-INTA-Pad20)") (class "Default")
      (node (ref "IC4") (pin "20") (pinfunction "INTA_20") (pintype "output"))
    )
    (net (code "141") (name "unconnected-(IC4-INTB-Pad19)") (class "Default")
      (node (ref "IC4") (pin "19") (pinfunction "INTB_19") (pintype "output"))
    )
    (net (code "142") (name "unconnected-(IC5A-R2IN-Pad8)") (class "Default")
      (node (ref "IC5") (pin "8") (pinfunction "R2IN_8") (pintype "input"))
    )
    (net (code "143") (name "unconnected-(IC5A-R2OUT-Pad9)") (class "Default")
      (node (ref "IC5") (pin "9") (pinfunction "R2OUT_9") (pintype "output"))
    )
    (net (code "144") (name "unconnected-(IC5A-T2IN-Pad10)") (class "Default")
      (node (ref "IC5") (pin "10") (pinfunction "T2IN_10") (pintype "input"))
    )
    (net (code "145") (name "unconnected-(IC5A-T2OUT-Pad7)") (class "Default")
      (node (ref "IC5") (pin "7") (pinfunction "T2OUT_7") (pintype "output"))
    )
    (net (code "146") (name "unconnected-(IC6-3V3OUT-Pad17)") (class "Default")
      (node (ref "IC6") (pin "17") (pinfunction "3V3OUT_17") (pintype "output"))
    )
    (net (code "147") (name "unconnected-(IC6-CBUS2-Pad13)") (class "Default")
      (node (ref "IC6") (pin "13") (pinfunction "CBUS2_13") (pintype "bidirectional"))
    )
    (net (code "148") (name "unconnected-(IC6-CBUS3-Pad14)") (class "Default")
      (node (ref "IC6") (pin "14") (pinfunction "CBUS3_14") (pintype "bidirectional"))
    )
    (net (code "149") (name "unconnected-(IC6-CBUS4-Pad12)") (class "Default")
      (node (ref "IC6") (pin "12") (pinfunction "CBUS4_12") (pintype "bidirectional"))
    )
    (net (code "150") (name "unconnected-(IC6-OSCI-Pad27)") (class "Default")
      (node (ref "IC6") (pin "27") (pinfunction "OSCI_27") (pintype "input"))
    )
    (net (code "151") (name "unconnected-(IC6-OSCO-Pad28)") (class "Default")
      (node (ref "IC6") (pin "28") (pinfunction "OSCO_28") (pintype "output"))
    )
    (net (code "152") (name "unconnected-(IC6-~{CTS}-Pad11)") (class "Default")
      (node (ref "IC6") (pin "11") (pinfunction "~{CTS}_11") (pintype "input"))
    )
    (net (code "153") (name "unconnected-(IC6-~{DCD}-Pad10)") (class "Default")
      (node (ref "IC6") (pin "10") (pinfunction "~{DCD}_10") (pintype "input"))
    )
    (net (code "154") (name "unconnected-(IC6-~{DSR}-Pad9)") (class "Default")
      (node (ref "IC6") (pin "9") (pinfunction "~{DSR}_9") (pintype "input"))
    )
    (net (code "155") (name "unconnected-(IC6-~{DTR}-Pad2)") (class "Default")
      (node (ref "IC6") (pin "2") (pinfunction "~{DTR}_2") (pintype "output"))
    )
    (net (code "156") (name "unconnected-(IC6-~{RESET}-Pad19)") (class "Default")
      (node (ref "IC6") (pin "19") (pinfunction "~{RESET}_19") (pintype "input"))
    )
    (net (code "157") (name "unconnected-(IC6-~{RI}-Pad6)") (class "Default")
      (node (ref "IC6") (pin "6") (pinfunction "~{RI}_6") (pintype "input"))
    )
    (net (code "158") (name "unconnected-(IC6-~{RTS}-Pad3)") (class "Default")
      (node (ref "IC6") (pin "3") (pinfunction "~{RTS}_3") (pintype "output"))
    )
    (net (code "159") (name "unconnected-(IC7-OUT1-PadTAB)") (class "Default")
      (node (ref "IC7") (pin "TAB") (pinfunction "OUT1_TAB") (pintype "passive"))
    )
    (net (code "160") (name "unconnected-(SV1-Pad5)") (class "Default")
      (node (ref "SV1") (pin "5") (pinfunction "5_5") (pintype "passive"))
    )
    (net (code "161") (name "unconnected-(U$1-Pad1')") (class "Default")
      (node (ref "U$1") (pin "1'") (pinfunction "1'_1'") (pintype "output"))
    )
    (net (code "162") (name "unconnected-(U$1-Pad1)") (class "Default")
      (node (ref "U$1") (pin "1") (pinfunction "1_1") (pintype "output"))
    )
    (net (code "163") (name "unconnected-(U$1-Pad2')") (class "Default")
      (node (ref "U$1") (pin "2'") (pinfunction "2'_2'") (pintype "output"))
    )
    (net (code "164") (name "unconnected-(U$1-Pad3')") (class "Default")
      (node (ref "U$1") (pin "3'") (pinfunction "3'_3'") (pintype "output"))
    )
    (net (code "165") (name "unconnected-(U$1-Pad4')") (class "Default")
      (node (ref "U$1") (pin "4'") (pinfunction "4'_4'") (pintype "output"))
    )
    (net (code "166") (name "unconnected-(U$1-Pad5')") (class "Default")
      (node (ref "U$1") (pin "5'") (pinfunction "5'_5'") (pintype "output"))
    )
    (net (code "167") (name "unconnected-(U$1-Pad6')") (class "Default")
      (node (ref "U$1") (pin "6'") (pinfunction "6'_6'") (pintype "output"))
    )
    (net (code "168") (name "unconnected-(U$1-Pad7A)") (class "Default")
      (node (ref "U$1") (pin "7A") (pinfunction "7A_7A") (pintype "output"))
    )
    (net (code "169") (name "unconnected-(U$1-Pad8)") (class "Default")
      (node (ref "U$1") (pin "8") (pinfunction "8_8") (pintype "output"))
    )
    (net (code "170") (name "unconnected-(U$1-Pad8A)") (class "Default")
      (node (ref "U$1") (pin "8A") (pinfunction "8A_8A") (pintype "output"))
    )
    (net (code "171") (name "unconnected-(U$1-Pad9A)") (class "Default")
      (node (ref "U$1") (pin "9A") (pinfunction "9A_9A") (pintype "output"))
    )
    (net (code "172") (name "unconnected-(U$1-Pad10A)") (class "Default")
      (node (ref "U$1") (pin "10A") (pinfunction "10A_10A") (pintype "output"))
    )
    (net (code "173") (name "unconnected-(U$1-Pad11')") (class "Default")
      (node (ref "U$1") (pin "11'") (pinfunction "11'_11'") (pintype "output"))
    )
    (net (code "174") (name "unconnected-(U$1-Pad12')") (class "Default")
      (node (ref "U$1") (pin "12'") (pinfunction "12'_12'") (pintype "output"))
    )
    (net (code "175") (name "unconnected-(U$1-Pad13')") (class "Default")
      (node (ref "U$1") (pin "13'") (pinfunction "13'_13'") (pintype "output"))
    )
    (net (code "176") (name "unconnected-(U$1-Pad14')") (class "Default")
      (node (ref "U$1") (pin "14'") (pinfunction "14'_14'") (pintype "output"))
    )
    (net (code "177") (name "unconnected-(U$1-Pad15')") (class "Default")
      (node (ref "U$1") (pin "15'") (pinfunction "15'_15'") (pintype "output"))
    )
    (net (code "178") (name "unconnected-(U$1-Pad16')") (class "Default")
      (node (ref "U$1") (pin "16'") (pinfunction "16'_16'") (pintype "output"))
    )
    (net (code "179") (name "unconnected-(U$1-Pad17A)") (class "Default")
      (node (ref "U$1") (pin "17A") (pinfunction "17A_17A") (pintype "output"))
    )
    (net (code "180") (name "unconnected-(U$1-Pad17B)") (class "Default")
      (node (ref "U$1") (pin "17B") (pinfunction "17B_17B") (pintype "output"))
    )
    (net (code "181") (name "unconnected-(U$1-Pad18')") (class "Default")
      (node (ref "U$1") (pin "18'") (pinfunction "18'_18'") (pintype "output"))
    )
    (net (code "182") (name "unconnected-(U$1-Pad18)") (class "Default")
      (node (ref "U$1") (pin "18") (pinfunction "18_18") (pintype "output"))
    )
    (net (code "183") (name "unconnected-(U$1-Pad19')") (class "Default")
      (node (ref "U$1") (pin "19'") (pinfunction "19'_19'") (pintype "output"))
    )
    (net (code "184") (name "unconnected-(U$1-Pad19)") (class "Default")
      (node (ref "U$1") (pin "19") (pinfunction "19_19") (pintype "output"))
    )
    (net (code "185") (name "unconnected-(U$1-Pad20)") (class "Default")
      (node (ref "U$1") (pin "20") (pinfunction "20_20") (pintype "output"))
    )
    (net (code "186") (name "unconnected-(U$1-Pad20A)") (class "Default")
      (node (ref "U$1") (pin "20A") (pinfunction "20A_20A") (pintype "output"))
    )
    (net (code "187") (name "unconnected-(U$1-Pad21)") (class "Default")
      (node (ref "U$1") (pin "21") (pinfunction "21_21") (pintype "output"))
    )
    (net (code "188") (name "unconnected-(U$1-Pad21A)") (class "Default")
      (node (ref "U$1") (pin "21A") (pinfunction "21A_21A") (pintype "output"))
    )
    (net (code "189") (name "unconnected-(U$1-Pad22')") (class "Default")
      (node (ref "U$1") (pin "22'") (pinfunction "22'_22'") (pintype "output"))
    )
    (net (code "190") (name "unconnected-(U$1-Pad23')") (class "Default")
      (node (ref "U$1") (pin "23'") (pinfunction "23'_23'") (pintype "output"))
    )
    (net (code "191") (name "unconnected-(U$1-Pad24')") (class "Default")
      (node (ref "U$1") (pin "24'") (pinfunction "24'_24'") (pintype "output"))
    )
    (net (code "192") (name "unconnected-(U$1-Pad25')") (class "Default")
      (node (ref "U$1") (pin "25'") (pinfunction "25'_25'") (pintype "output"))
    )
    (net (code "193") (name "unconnected-(U$1-Pad26')") (class "Default")
      (node (ref "U$1") (pin "26'") (pinfunction "26'_26'") (pintype "output"))
    )
    (net (code "194") (name "unconnected-(U$1-Pad27')") (class "Default")
      (node (ref "U$1") (pin "27'") (pinfunction "27'_27'") (pintype "output"))
    )
    (net (code "195") (name "unconnected-(U$1-Pad28')") (class "Default")
      (node (ref "U$1") (pin "28'") (pinfunction "28'_28'") (pintype "output"))
    )
    (net (code "196") (name "unconnected-(U$1-Pad29')") (class "Default")
      (node (ref "U$1") (pin "29'") (pinfunction "29'_29'") (pintype "output"))
    )
    (net (code "197") (name "unconnected-(U$1-Pad30')") (class "Default")
      (node (ref "U$1") (pin "30'") (pinfunction "30'_30'") (pintype "output"))
    )
    (net (code "198") (name "unconnected-(U$1-Pad31')") (class "Default")
      (node (ref "U$1") (pin "31'") (pinfunction "31'_31'") (pintype "output"))
    )
    (net (code "199") (name "unconnected-(U$1-Pad32')") (class "Default")
      (node (ref "U$1") (pin "32'") (pinfunction "32'_32'") (pintype "output"))
    )
    (net (code "200") (name "unconnected-(U$1-Pad33')") (class "Default")
      (node (ref "U$1") (pin "33'") (pinfunction "33'_33'") (pintype "output"))
    )
    (net (code "201") (name "unconnected-(U$1-Pad34')") (class "Default")
      (node (ref "U$1") (pin "34'") (pinfunction "34'_34'") (pintype "output"))
    )
    (net (code "202") (name "unconnected-(U$1-Pad35)") (class "Default")
      (node (ref "U$1") (pin "35") (pinfunction "35_35") (pintype "output"))
    )
    (net (code "203") (name "unconnected-(U$1-Pad35A)") (class "Default")
      (node (ref "U$1") (pin "35A") (pinfunction "35A_35A") (pintype "output"))
    )
    (net (code "204") (name "unconnected-(U$1-Pad36')") (class "Default")
      (node (ref "U$1") (pin "36'") (pinfunction "36'_36'") (pintype "output"))
    )
    (net (code "205") (name "unconnected-(U$1-Pad37')") (class "Default")
      (node (ref "U$1") (pin "37'") (pinfunction "37'_37'") (pintype "output"))
    )
    (net (code "206") (name "unconnected-(U$1-Pad38')") (class "Default")
      (node (ref "U$1") (pin "38'") (pinfunction "38'_38'") (pintype "output"))
    )
    (net (code "207") (name "unconnected-(U$1-Pad39')") (class "Default")
      (node (ref "U$1") (pin "39'") (pinfunction "39'_39'") (pintype "output"))
    )
    (net (code "208") (name "unconnected-(U$1-Pad40')") (class "Default")
      (node (ref "U$1") (pin "40'") (pinfunction "40'_40'") (pintype "output"))
    )
    (net (code "209") (name "unconnected-(U$1-Pad41')") (class "Default")
      (node (ref "U$1") (pin "41'") (pinfunction "41'_41'") (pintype "output"))
    )
    (net (code "210") (name "unconnected-(U$1-Pad42')") (class "Default")
      (node (ref "U$1") (pin "42'") (pinfunction "42'_42'") (pintype "output"))
    )
    (net (code "211") (name "unconnected-(U$1-Pad43')") (class "Default")
      (node (ref "U$1") (pin "43'") (pinfunction "43'_43'") (pintype "output"))
    )
    (net (code "212") (name "unconnected-(U$1-Pad44')") (class "Default")
      (node (ref "U$1") (pin "44'") (pinfunction "44'_44'") (pintype "output"))
    )
    (net (code "213") (name "unconnected-(U$1-Pad45')") (class "Default")
      (node (ref "U$1") (pin "45'") (pinfunction "45'_45'") (pintype "output"))
    )
    (net (code "214") (name "unconnected-(U$1-Pad46')") (class "Default")
      (node (ref "U$1") (pin "46'") (pinfunction "46'_46'") (pintype "output"))
    )
    (net (code "215") (name "unconnected-(U$1-Pad47')") (class "Default")
      (node (ref "U$1") (pin "47'") (pinfunction "47'_47'") (pintype "output"))
    )
    (net (code "216") (name "unconnected-(U$1-Pad47)") (class "Default")
      (node (ref "U$1") (pin "47") (pinfunction "47_47") (pintype "output"))
    )
    (net (code "217") (name "unconnected-(U$1-Pad48')") (class "Default")
      (node (ref "U$1") (pin "48'") (pinfunction "48'_48'") (pintype "output"))
    )
    (net (code "218") (name "unconnected-(U$1-Pad48)") (class "Default")
      (node (ref "U$1") (pin "48") (pinfunction "48_48") (pintype "output"))
    )
    (net (code "219") (name "unconnected-(U$1-Pad49')") (class "Default")
      (node (ref "U$1") (pin "49'") (pinfunction "49'_49'") (pintype "output"))
    )
    (net (code "220") (name "unconnected-(U$1-Pad49)") (class "Default")
      (node (ref "U$1") (pin "49") (pinfunction "49_49") (pintype "output"))
    )
    (net (code "221") (name "unconnected-(U$1-Pad50')") (class "Default")
      (node (ref "U$1") (pin "50'") (pinfunction "50'_50'") (pintype "output"))
    )
    (net (code "222") (name "unconnected-(U$1-Pad51')") (class "Default")
      (node (ref "U$1") (pin "51'") (pinfunction "51'_51'") (pintype "output"))
    )
    (net (code "223") (name "unconnected-(U$1-Pad52')") (class "Default")
      (node (ref "U$1") (pin "52'") (pinfunction "52'_52'") (pintype "output"))
    )
    (net (code "224") (name "unconnected-(U$1-Pad53')") (class "Default")
      (node (ref "U$1") (pin "53'") (pinfunction "53'_53'") (pintype "output"))
    )
    (net (code "225") (name "unconnected-(U$1-Pad54')") (class "Default")
      (node (ref "U$1") (pin "54'") (pinfunction "54'_54'") (pintype "output"))
    )
    (net (code "226") (name "unconnected-(U$1-Pad55')") (class "Default")
      (node (ref "U$1") (pin "55'") (pinfunction "55'_55'") (pintype "output"))
    )
    (net (code "227") (name "unconnected-(U$1-Pad57)") (class "Default")
      (node (ref "U$1") (pin "57") (pinfunction "57_57") (pintype "output"))
    )
    (net (code "228") (name "unconnected-(U$1-Pad57A)") (class "Default")
      (node (ref "U$1") (pin "57A") (pinfunction "57A_57A") (pintype "output"))
    )
    (net (code "229") (name "unconnected-(U$1-Pad58)") (class "Default")
      (node (ref "U$1") (pin "58") (pinfunction "58_58") (pintype "output"))
    )
    (net (code "230") (name "unconnected-(U$1-Pad58A)") (class "Default")
      (node (ref "U$1") (pin "58A") (pinfunction "58A_58A") (pintype "output"))
    )
    (net (code "231") (name "unconnected-(U$1-Pad59)") (class "Default")
      (node (ref "U$1") (pin "59") (pinfunction "59_59") (pintype "output"))
    )
    (net (code "232") (name "unconnected-(U$1-Pad59A)") (class "Default")
      (node (ref "U$1") (pin "59A") (pinfunction "59A_59A") (pintype "output"))
    )
    (net (code "233") (name "unconnected-(U$1-Pad60)") (class "Default")
      (node (ref "U$1") (pin "60") (pinfunction "60_60") (pintype "output"))
    )
    (net (code "234") (name "unconnected-(U$1-Pad60A)") (class "Default")
      (node (ref "U$1") (pin "60A") (pinfunction "60A_60A") (pintype "output"))
    )
    (net (code "235") (name "unconnected-(U$1-Pad61')") (class "Default")
      (node (ref "U$1") (pin "61'") (pinfunction "61'_61'") (pintype "output"))
    )
    (net (code "236") (name "unconnected-(U$1-Pad61)") (class "Default")
      (node (ref "U$1") (pin "61") (pinfunction "61_61") (pintype "output"))
    )
    (net (code "237") (name "unconnected-(U$1-Pad62')") (class "Default")
      (node (ref "U$1") (pin "62'") (pinfunction "62'_62'") (pintype "output"))
    )
    (net (code "238") (name "unconnected-(U$1-Pad63')") (class "Default")
      (node (ref "U$1") (pin "63'") (pinfunction "63'_63'") (pintype "output"))
    )
    (net (code "239") (name "unconnected-(U$1-Pad64')") (class "Default")
      (node (ref "U$1") (pin "64'") (pinfunction "64'_64'") (pintype "output"))
    )
    (net (code "240") (name "unconnected-(U$1-Pad64)") (class "Default")
      (node (ref "U$1") (pin "64") (pinfunction "64_64") (pintype "output"))
    )
    (net (code "241") (name "unconnected-(U$1-Pad65')") (class "Default")
      (node (ref "U$1") (pin "65'") (pinfunction "65'_65'") (pintype "output"))
    )
    (net (code "242") (name "unconnected-(U$1-Pad65)") (class "Default")
      (node (ref "U$1") (pin "65") (pinfunction "65_65") (pintype "output"))
    )
    (net (code "243") (name "unconnected-(U$1-Pad66')") (class "Default")
      (node (ref "U$1") (pin "66'") (pinfunction "66'_66'") (pintype "output"))
    )
    (net (code "244") (name "unconnected-(U$1-Pad66)") (class "Default")
      (node (ref "U$1") (pin "66") (pinfunction "66_66") (pintype "output"))
    )
    (net (code "245") (name "unconnected-(U$1-Pad67')") (class "Default")
      (node (ref "U$1") (pin "67'") (pinfunction "67'_67'") (pintype "output"))
    )
    (net (code "246") (name "unconnected-(U$1-Pad67)") (class "Default")
      (node (ref "U$1") (pin "67") (pinfunction "67_67") (pintype "output"))
    )
    (net (code "247") (name "unconnected-(U$1-Pad68')") (class "Default")
      (node (ref "U$1") (pin "68'") (pinfunction "68'_68'") (pintype "output"))
    )
    (net (code "248") (name "unconnected-(U$1-Pad68)") (class "Default")
      (node (ref "U$1") (pin "68") (pinfunction "68_68") (pintype "output"))
    )
    (net (code "249") (name "unconnected-(U$1-Pad69')") (class "Default")
      (node (ref "U$1") (pin "69'") (pinfunction "69'_69'") (pintype "output"))
    )
    (net (code "250") (name "unconnected-(U$1-Pad70')") (class "Default")
      (node (ref "U$1") (pin "70'") (pinfunction "70'_70'") (pintype "output"))
    )
    (net (code "251") (name "unconnected-(U$1-Pad71')") (class "Default")
      (node (ref "U$1") (pin "71'") (pinfunction "71'_71'") (pintype "output"))
    )
    (net (code "252") (name "unconnected-(U$1-Pad72')") (class "Default")
      (node (ref "U$1") (pin "72'") (pinfunction "72'_72'") (pintype "output"))
    )
    (net (code "253") (name "unconnected-(U$1-Pad72)") (class "Default")
      (node (ref "U$1") (pin "72") (pinfunction "72_72") (pintype "output"))
    )
    (net (code "254") (name "unconnected-(U$1-Pad73')") (class "Default")
      (node (ref "U$1") (pin "73'") (pinfunction "73'_73'") (pintype "output"))
    )
    (net (code "255") (name "unconnected-(U$1-Pad74')") (class "Default")
      (node (ref "U$1") (pin "74'") (pinfunction "74'_74'") (pintype "output"))
    )
    (net (code "256") (name "unconnected-(U$2-3.3-2-Pad17)") (class "Default")
      (node (ref "U$2") (pin "17") (pinfunction "3.3-2_17") (pintype "bidirectional"))
    )
    (net (code "257") (name "unconnected-(U$2-12-Pad32)") (class "Default")
      (node (ref "U$2") (pin "32") (pinfunction "12_32") (pintype "bidirectional"))
    )
  )
)
